# Rwanda-AC-CurrentSense.net
KiCad netlist of a schematic drawn in EAGLE
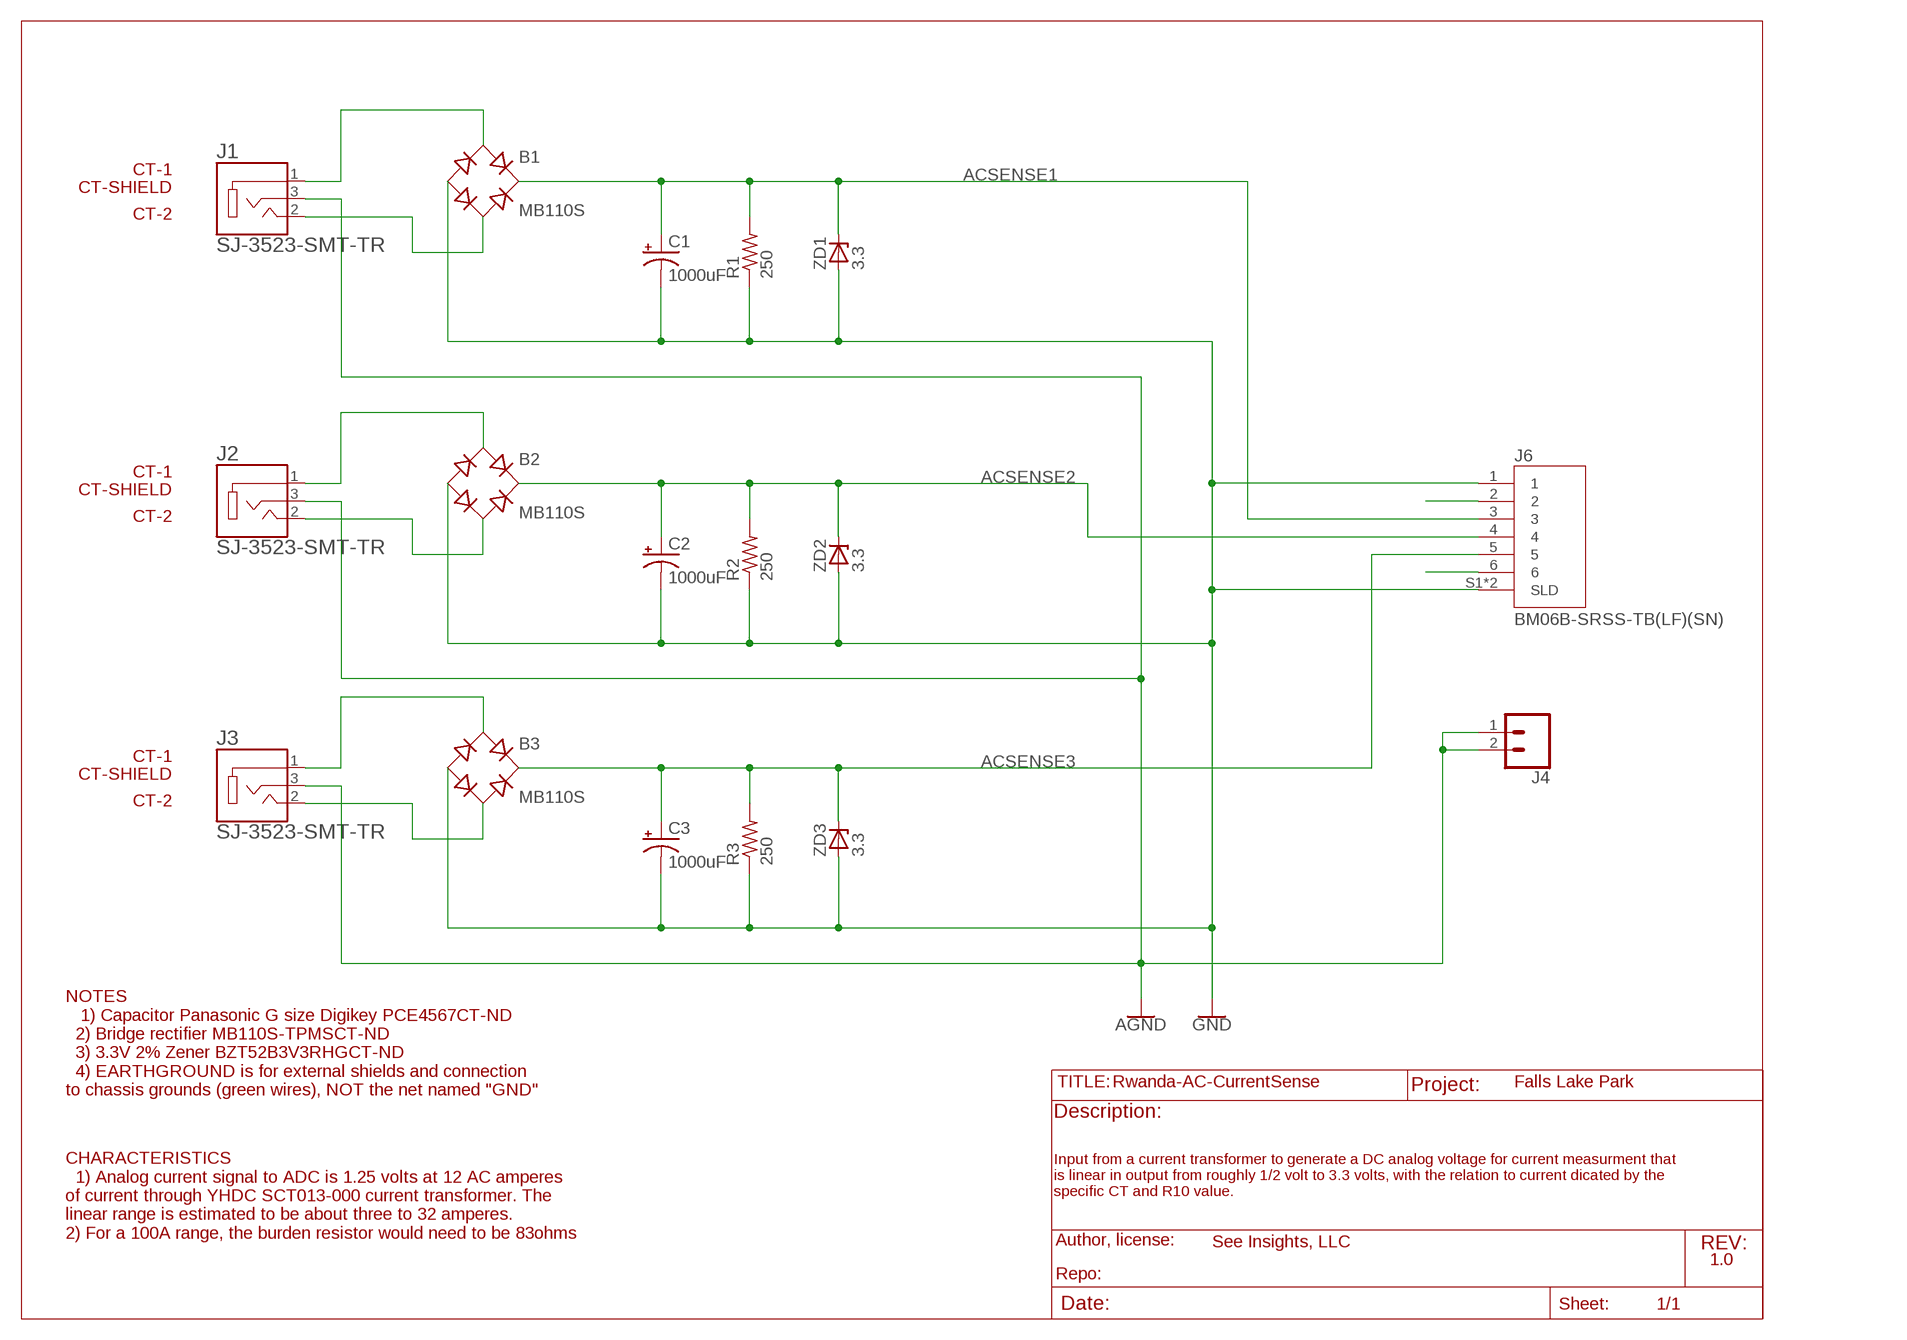
[diagram p0: schematic, sheet 1]

(export (version "E")
  (design (tool "Eeschema 10.0.6"))
  (components
    (comp (ref "B1")
      (value "MB110S")
      (footprint "eagle-import:SOIC-4")
      (fields (field (name "MPN") "MB1S"))
      (libsource (lib "eagle-import") (part "MBS1"))
    )
    (comp (ref "B2")
      (value "MB110S")
      (footprint "eagle-import:SOIC-4")
      (libsource (lib "eagle-import") (part "MBS1"))
    )
    (comp (ref "B3")
      (value "MB110S")
      (footprint "eagle-import:SOIC-4")
      (libsource (lib "eagle-import") (part "MBS1"))
    )
    (comp (ref "C1")
      (value "1000uF")
      (footprint "eagle-import:PANASONIC_G")
      (libsource (lib "eagle-import") (part "CPOL-USG"))
    )
    (comp (ref "C2")
      (value "1000uF")
      (footprint "eagle-import:PANASONIC_G")
      (libsource (lib "eagle-import") (part "CPOL-USG"))
    )
    (comp (ref "C3")
      (value "1000uF")
      (footprint "eagle-import:PANASONIC_G")
      (libsource (lib "eagle-import") (part "CPOL-USG"))
    )
    (comp (ref "J1")
      (value "SJ-3523-SMT-TR")
      (footprint "eagle-import:CUI_SJ-3523-SMT-TR")
      (fields (field (name "DIGI-KEY_PART_NUMBER") "CP-3523SJCT-ND") (field (name "MF") "CUI Inc."))
      (libsource (lib "eagle-import") (part "SJ-3523-SMT-TR"))
    )
    (comp (ref "J2")
      (value "SJ-3523-SMT-TR")
      (footprint "eagle-import:CUI_SJ-3523-SMT-TR")
      (fields (field (name "DIGI-KEY_PART_NUMBER") "CP-3523SJCT-ND") (field (name "MF") "CUI Inc."))
      (libsource (lib "eagle-import") (part "SJ-3523-SMT-TR"))
    )
    (comp (ref "J3")
      (value "SJ-3523-SMT-TR")
      (footprint "eagle-import:CUI_SJ-3523-SMT-TR")
      (fields (field (name "DIGI-KEY_PART_NUMBER") "CP-3523SJCT-ND") (field (name "MF") "CUI Inc."))
      (libsource (lib "eagle-import") (part "SJ-3523-SMT-TR"))
    )
    (comp (ref "J4")
      (value "CONN_02")
      (footprint "eagle-import:1X02")
      (libsource (lib "eagle-import") (part "CONN_02"))
    )
    (comp (ref "J6")
      (value "BM06B-SRSS-TB(LF)(SN)")
      (footprint "eagle-import:JST_BM06B-SRSS-TB(LF)(SN)")
      (libsource (lib "eagle-import") (part "BM06B-SRSS-TB(LF)(SN)"))
    )
    (comp (ref "R1")
      (value "250")
      (footprint "eagle-import:M1206")
      (libsource (lib "eagle-import") (part "R-US_M1206"))
    )
    (comp (ref "R2")
      (value "250")
      (footprint "eagle-import:M1206")
      (libsource (lib "eagle-import") (part "R-US_M1206"))
    )
    (comp (ref "R3")
      (value "250")
      (footprint "eagle-import:M1206")
      (fields (field (name "MPN") "CR1206-FX-2202ELF"))
      (libsource (lib "eagle-import") (part "R-US_M1206"))
    )
    (comp (ref "ZD1")
      (value "3.3")
      (footprint "eagle-import:SOD123")
      (libsource (lib "eagle-import") (part "ZD-SOD123"))
    )
    (comp (ref "ZD2")
      (value "3.3")
      (footprint "eagle-import:SOD123")
      (libsource (lib "eagle-import") (part "ZD-SOD123"))
    )
    (comp (ref "ZD3")
      (value "3.3")
      (footprint "eagle-import:SOD123")
      (fields (field (name "MPN") "BZT52B3V3 RHG"))
      (libsource (lib "eagle-import") (part "ZD-SOD123"))
    )
  )
  (nets
    (net (code "1") (name "/ACSENSE1") (class "Default")
      (node (ref "B1") (pin "+") (pinfunction "+_+") (pintype "passive"))
      (node (ref "C1") (pin "+") (pinfunction "+_+") (pintype "passive"))
      (node (ref "J6") (pin "3") (pinfunction "3_3") (pintype "passive"))
      (node (ref "R1") (pin "2") (pinfunction "2_2") (pintype "passive"))
      (node (ref "ZD1") (pin "C") (pinfunction "C_C") (pintype "passive"))
    )
    (net (code "2") (name "/ACSENSE2") (class "Default")
      (node (ref "B2") (pin "+") (pinfunction "+_+") (pintype "passive"))
      (node (ref "C2") (pin "+") (pinfunction "+_+") (pintype "passive"))
      (node (ref "J6") (pin "4") (pinfunction "4_4") (pintype "passive"))
      (node (ref "R2") (pin "2") (pinfunction "2_2") (pintype "passive"))
      (node (ref "ZD2") (pin "C") (pinfunction "C_C") (pintype "passive"))
    )
    (net (code "3") (name "/ACSENSE3") (class "Default")
      (node (ref "B3") (pin "+") (pinfunction "+_+") (pintype "passive"))
      (node (ref "C3") (pin "+") (pinfunction "+_+") (pintype "passive"))
      (node (ref "J6") (pin "5") (pinfunction "5_5") (pintype "passive"))
      (node (ref "R3") (pin "2") (pinfunction "2_2") (pintype "passive"))
      (node (ref "ZD3") (pin "C") (pinfunction "C_C") (pintype "passive"))
    )
    (net (code "4") (name "AGND") (class "Default")
      (node (ref "J1") (pin "3") (pinfunction "3_3") (pintype "passive"))
      (node (ref "J2") (pin "3") (pinfunction "3_3") (pintype "passive"))
      (node (ref "J3") (pin "3") (pinfunction "3_3") (pintype "passive"))
      (node (ref "J4") (pin "1") (pinfunction "1_1") (pintype "passive"))
      (node (ref "J4") (pin "2") (pinfunction "2_2") (pintype "passive"))
    )
    (net (code "5") (name "GND") (class "Default")
      (node (ref "B1") (pin "-") (pinfunction "-_-") (pintype "passive"))
      (node (ref "B2") (pin "-") (pinfunction "-_-") (pintype "passive"))
      (node (ref "B3") (pin "-") (pinfunction "-_-") (pintype "passive"))
      (node (ref "C1") (pin "-") (pinfunction "-_-") (pintype "passive"))
      (node (ref "C2") (pin "-") (pinfunction "-_-") (pintype "passive"))
      (node (ref "C3") (pin "-") (pinfunction "-_-") (pintype "passive"))
      (node (ref "J6") (pin "1") (pinfunction "1_1") (pintype "passive"))
      (node (ref "J6") (pin "S1") (pinfunction "SLD_S1") (pintype "passive"))
      (node (ref "J6") (pin "S2") (pinfunction "SLD_S2") (pintype "passive"))
      (node (ref "R1") (pin "1") (pinfunction "1_1") (pintype "passive"))
      (node (ref "R2") (pin "1") (pinfunction "1_1") (pintype "passive"))
      (node (ref "R3") (pin "1") (pinfunction "1_1") (pintype "passive"))
      (node (ref "ZD1") (pin "A") (pinfunction "A_A") (pintype "passive"))
      (node (ref "ZD2") (pin "A") (pinfunction "A_A") (pintype "passive"))
      (node (ref "ZD3") (pin "A") (pinfunction "A_A") (pintype "passive"))
    )
    (net (code "6") (name "Net-(B1-AC1)") (class "Default")
      (node (ref "B1") (pin "~1") (pinfunction "AC1_~1") (pintype "passive"))
      (node (ref "J1") (pin "1") (pinfunction "1_1") (pintype "passive"))
    )
    (net (code "7") (name "Net-(B1-AC2)") (class "Default")
      (node (ref "B1") (pin "~2") (pinfunction "AC2_~2") (pintype "passive"))
      (node (ref "J1") (pin "2") (pinfunction "2_2") (pintype "passive"))
    )
    (net (code "8") (name "Net-(B2-AC1)") (class "Default")
      (node (ref "B2") (pin "~1") (pinfunction "AC1_~1") (pintype "passive"))
      (node (ref "J2") (pin "1") (pinfunction "1_1") (pintype "passive"))
    )
    (net (code "9") (name "Net-(B2-AC2)") (class "Default")
      (node (ref "B2") (pin "~2") (pinfunction "AC2_~2") (pintype "passive"))
      (node (ref "J2") (pin "2") (pinfunction "2_2") (pintype "passive"))
    )
    (net (code "10") (name "Net-(B3-AC1)") (class "Default")
      (node (ref "B3") (pin "~1") (pinfunction "AC1_~1") (pintype "passive"))
      (node (ref "J3") (pin "1") (pinfunction "1_1") (pintype "passive"))
    )
    (net (code "11") (name "Net-(B3-AC2)") (class "Default")
      (node (ref "B3") (pin "~2") (pinfunction "AC2_~2") (pintype "passive"))
      (node (ref "J3") (pin "2") (pinfunction "2_2") (pintype "passive"))
    )
    (net (code "12") (name "unconnected-(J6-Pad2)") (class "Default")
      (node (ref "J6") (pin "2") (pinfunction "2_2") (pintype "passive"))
    )
    (net (code "13") (name "unconnected-(J6-Pad6)") (class "Default")
      (node (ref "J6") (pin "6") (pinfunction "6_6") (pintype "passive"))
    )
  )
)
